# MIC_module.net
KiCad netlist of a schematic drawn in EAGLE
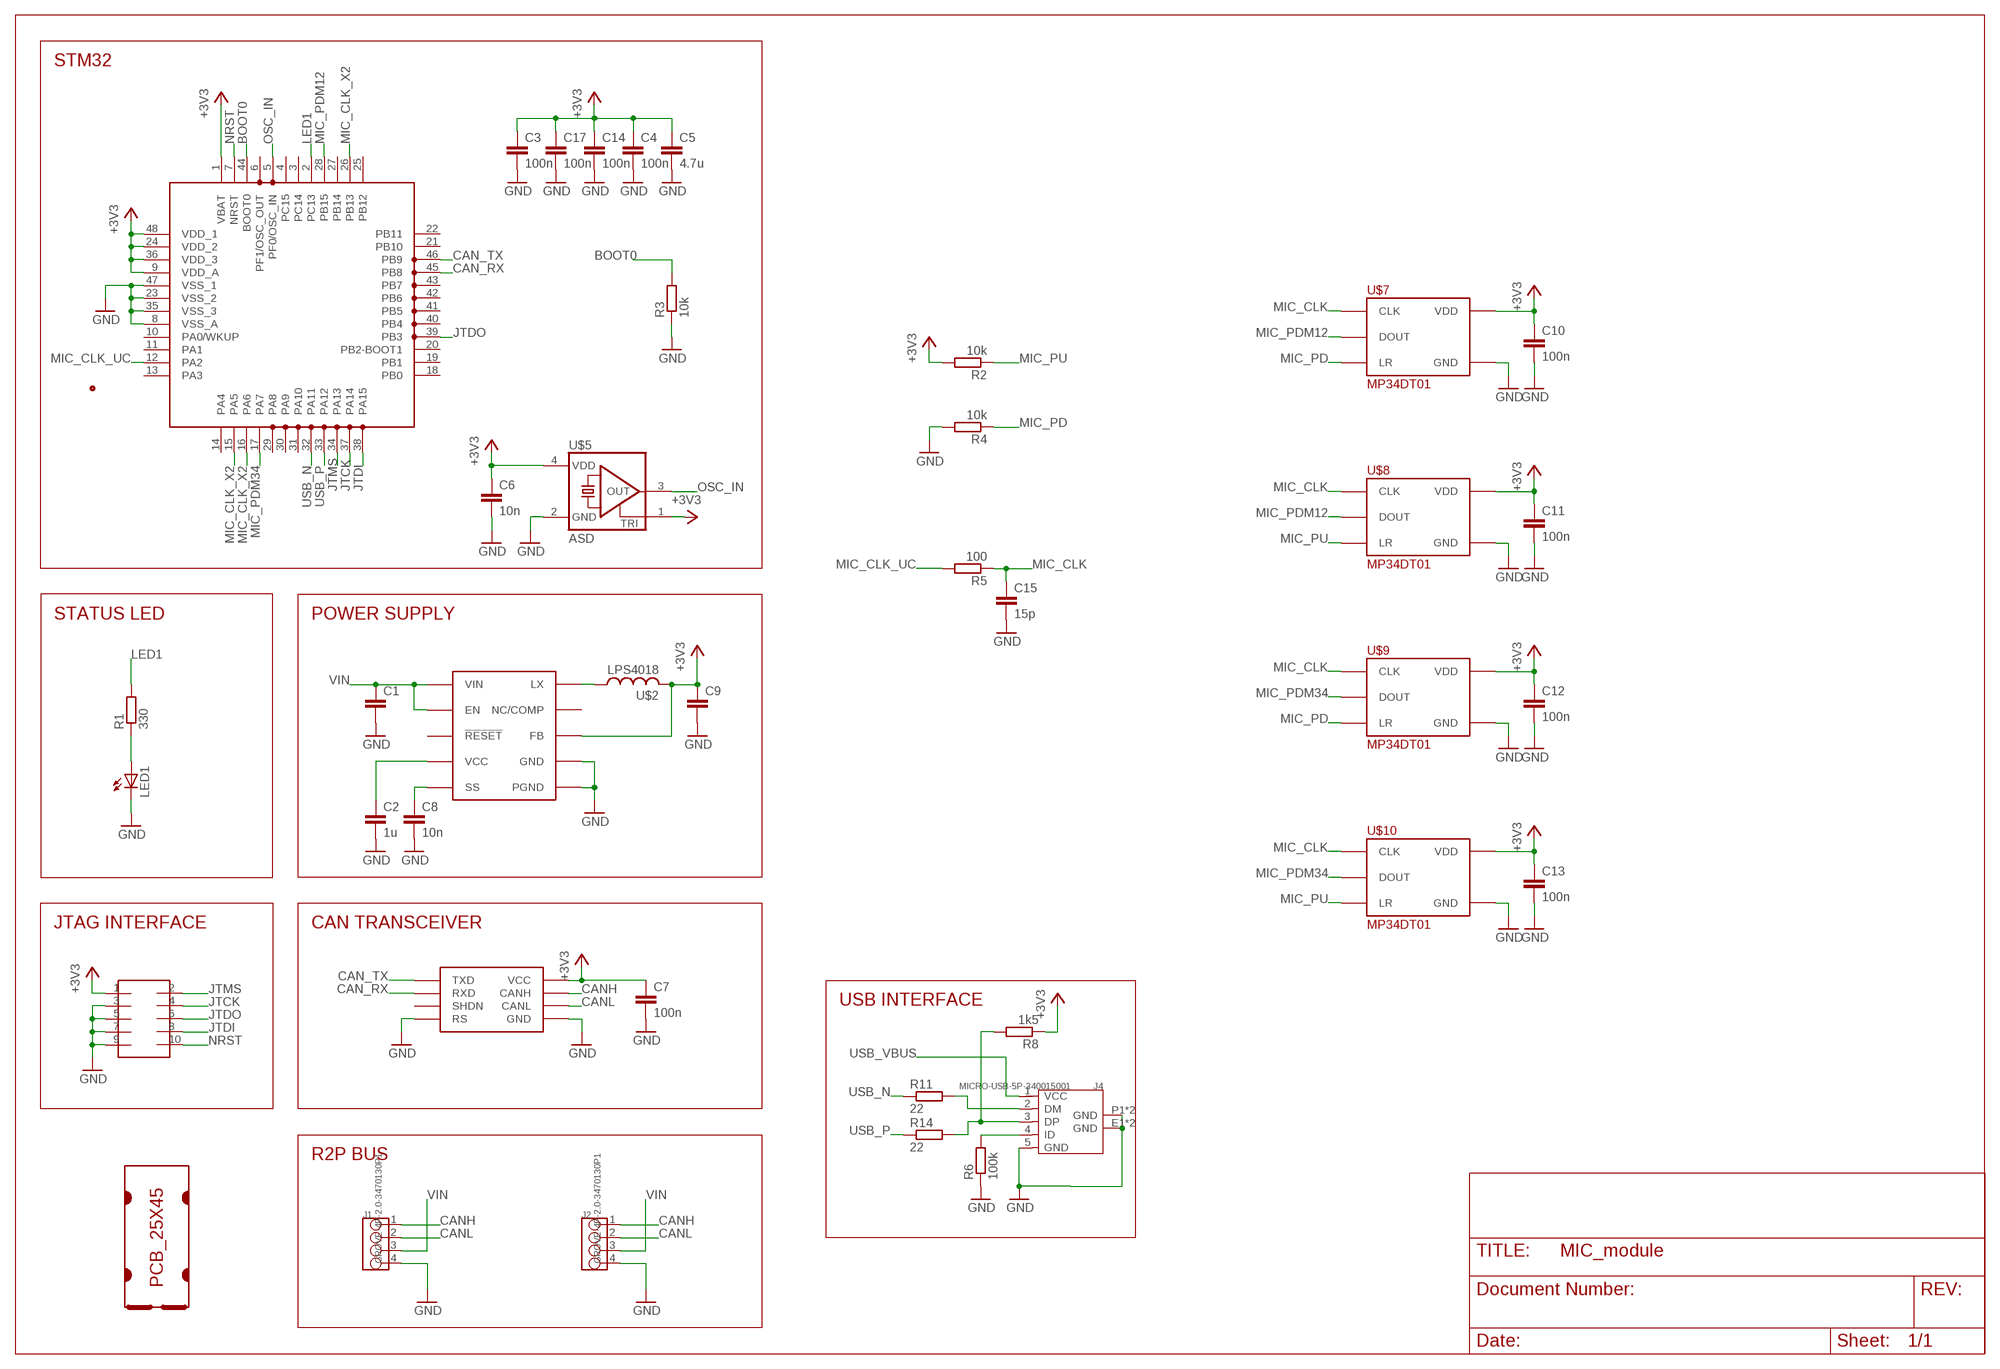
[diagram p0: schematic, sheet 1]

(export (version "E")
  (design (tool "Eeschema 10.0.6"))
  (components
    (comp (ref "C1")
      (value "C-EUC1206")
      (footprint "eagle-import:C1206")
      (libsource (lib "eagle-import") (part "C-EUC1206"))
    )
    (comp (ref "C2")
      (value "1u")
      (footprint "eagle-import:C0603")
      (libsource (lib "eagle-import") (part "C-EUC0603"))
    )
    (comp (ref "C3")
      (value "100n")
      (footprint "eagle-import:C0603")
      (libsource (lib "eagle-import") (part "C-EUC0603"))
    )
    (comp (ref "C4")
      (value "100n")
      (footprint "eagle-import:C0603")
      (libsource (lib "eagle-import") (part "C-EUC0603"))
    )
    (comp (ref "C5")
      (value "4.7u")
      (footprint "eagle-import:C0805")
      (libsource (lib "eagle-import") (part "C-EUC0805"))
    )
    (comp (ref "C6")
      (value "10n")
      (footprint "eagle-import:C0603")
      (libsource (lib "eagle-import") (part "C-EUC0603"))
    )
    (comp (ref "C7")
      (value "100n")
      (footprint "eagle-import:C0603")
      (libsource (lib "eagle-import") (part "C-EUC0603"))
    )
    (comp (ref "C8")
      (value "10n")
      (footprint "eagle-import:C0603")
      (libsource (lib "eagle-import") (part "C-EUC0603"))
    )
    (comp (ref "C9")
      (value "C-EUC0805")
      (footprint "eagle-import:C0805")
      (libsource (lib "eagle-import") (part "C-EUC0805"))
    )
    (comp (ref "C10")
      (value "100n")
      (footprint "eagle-import:C0603")
      (libsource (lib "eagle-import") (part "C-EUC0603"))
    )
    (comp (ref "C11")
      (value "100n")
      (footprint "eagle-import:C0603")
      (libsource (lib "eagle-import") (part "C-EUC0603"))
    )
    (comp (ref "C12")
      (value "100n")
      (footprint "eagle-import:C0603")
      (libsource (lib "eagle-import") (part "C-EUC0603"))
    )
    (comp (ref "C13")
      (value "100n")
      (footprint "eagle-import:C0603")
      (libsource (lib "eagle-import") (part "C-EUC0603"))
    )
    (comp (ref "C14")
      (value "100n")
      (footprint "eagle-import:C0603")
      (libsource (lib "eagle-import") (part "C-EUC0603"))
    )
    (comp (ref "C15")
      (value "15p")
      (footprint "eagle-import:C0603")
      (libsource (lib "eagle-import") (part "C-EUC0603"))
    )
    (comp (ref "C17")
      (value "100n")
      (footprint "eagle-import:C0603")
      (libsource (lib "eagle-import") (part "C-EUC0603"))
    )
    (comp (ref "J1")
      (value "GROVE-4P-2.0-3470130P1")
      (footprint "eagle-import:4P-2.0")
      (libsource (lib "eagle-import") (part "GROVE-4P-2.0-3470130P1"))
    )
    (comp (ref "J2")
      (value "GROVE-4P-2.0-3470130P1")
      (footprint "eagle-import:4P-2.0")
      (libsource (lib "eagle-import") (part "GROVE-4P-2.0-3470130P1"))
    )
    (comp (ref "J4")
      (value "MICRO-USB-5P-340015001")
      (footprint "eagle-import:B-SMD-5P")
      (libsource (lib "eagle-import") (part "MICRO-USB-5P-340015001"))
    )
    (comp (ref "LED1")
      (value "LEDCHIPLED_0805")
      (footprint "eagle-import:CHIPLED_0805")
      (libsource (lib "eagle-import") (part "LEDCHIPLED_0805"))
    )
    (comp (ref "R1")
      (value "330")
      (footprint "eagle-import:R0603")
      (libsource (lib "eagle-import") (part "R-EU_R0603"))
    )
    (comp (ref "R2")
      (value "10k")
      (footprint "eagle-import:R0603")
      (libsource (lib "eagle-import") (part "R-EU_R0603"))
    )
    (comp (ref "R3")
      (value "10k")
      (footprint "eagle-import:R0603")
      (libsource (lib "eagle-import") (part "R-EU_R0603"))
    )
    (comp (ref "R4")
      (value "10k")
      (footprint "eagle-import:R0603")
      (libsource (lib "eagle-import") (part "R-EU_R0603"))
    )
    (comp (ref "R5")
      (value "100")
      (footprint "eagle-import:R0603")
      (libsource (lib "eagle-import") (part "R-EU_R0603"))
    )
    (comp (ref "R6")
      (value "100k")
      (footprint "eagle-import:R0603")
      (libsource (lib "eagle-import") (part "R-EU_R0603"))
    )
    (comp (ref "R8")
      (value "1k5")
      (footprint "eagle-import:R0603")
      (libsource (lib "eagle-import") (part "R-EU_R0603"))
    )
    (comp (ref "R11")
      (value "22")
      (footprint "eagle-import:R0603")
      (libsource (lib "eagle-import") (part "R-EU_R0603"))
    )
    (comp (ref "R14")
      (value "22")
      (footprint "eagle-import:R0603")
      (libsource (lib "eagle-import") (part "R-EU_R0603"))
    )
    (comp (ref "SOT1")
      (value "MAX3051EKA")
      (footprint "eagle-import:SOT23-8L")
      (libsource (lib "eagle-import") (part "MAX3051EKA"))
    )
    (comp (ref "U$1")
      (value "PCB_25X45")
      (footprint "eagle-import:25X45")
      (libsource (lib "eagle-import") (part "PCB_25X45"))
    )
    (comp (ref "U$2")
      (value "LPS4018")
      (footprint "eagle-import:LPS4018")
      (libsource (lib "eagle-import") (part "LPS4018"))
    )
    (comp (ref "U$3")
      (value "MAX17501")
      (footprint "eagle-import:TDFN-10")
      (libsource (lib "eagle-import") (part "MAX17501"))
    )
    (comp (ref "U$4")
      (value "FTSH-105TH")
      (footprint "eagle-import:FTSH-105-TH")
      (libsource (lib "eagle-import") (part "FTSH-105TH"))
    )
    (comp (ref "U$5")
      (value "ASD")
      (footprint "eagle-import:2.5X2")
      (libsource (lib "eagle-import") (part "ASD"))
    )
    (comp (ref "U$6")
      (value "STM32F303C")
      (footprint "eagle-import:LQFP48")
      (libsource (lib "eagle-import") (part "STM32F303C"))
    )
    (comp (ref "U$7")
      (value "MP34DT01")
      (footprint "eagle-import:MP34DT01")
      (libsource (lib "eagle-import") (part "MP34DT01"))
    )
    (comp (ref "U$8")
      (value "MP34DT01")
      (footprint "eagle-import:MP34DT01")
      (libsource (lib "eagle-import") (part "MP34DT01"))
    )
    (comp (ref "U$9")
      (value "MP34DT01")
      (footprint "eagle-import:MP34DT01")
      (libsource (lib "eagle-import") (part "MP34DT01"))
    )
    (comp (ref "U$10")
      (value "MP34DT01")
      (footprint "eagle-import:MP34DT01")
      (libsource (lib "eagle-import") (part "MP34DT01"))
    )
  )
  (nets
    (net (code "1") (name "+3V3") (class "Default")
      (node (ref "C10") (pin "1") (pinfunction "1_1") (pintype "passive"))
      (node (ref "C11") (pin "1") (pinfunction "1_1") (pintype "passive"))
      (node (ref "C12") (pin "1") (pinfunction "1_1") (pintype "passive"))
      (node (ref "C13") (pin "1") (pinfunction "1_1") (pintype "passive"))
      (node (ref "C14") (pin "1") (pinfunction "1_1") (pintype "passive"))
      (node (ref "C17") (pin "1") (pinfunction "1_1") (pintype "passive"))
      (node (ref "C3") (pin "1") (pinfunction "1_1") (pintype "passive"))
      (node (ref "C4") (pin "1") (pinfunction "1_1") (pintype "passive"))
      (node (ref "C5") (pin "1") (pinfunction "1_1") (pintype "passive"))
      (node (ref "C6") (pin "1") (pinfunction "1_1") (pintype "passive"))
      (node (ref "C7") (pin "1") (pinfunction "1_1") (pintype "passive"))
      (node (ref "C9") (pin "1") (pinfunction "1_1") (pintype "passive"))
      (node (ref "R2") (pin "2") (pinfunction "2_2") (pintype "passive"))
      (node (ref "R8") (pin "1") (pinfunction "1_1") (pintype "passive"))
      (node (ref "SOT1") (pin "3") (pinfunction "VCC_3") (pintype "bidirectional"))
      (node (ref "U$10") (pin "P$1") (pinfunction "VDD_P$1") (pintype "bidirectional"))
      (node (ref "U$2") (pin "P$2") (pinfunction "2_P$2") (pintype "passive"))
      (node (ref "U$3") (pin "P$5") (pinfunction "FB_P$5") (pintype "bidirectional"))
      (node (ref "U$4") (pin "1") (pinfunction "P$1_1") (pintype "bidirectional"))
      (node (ref "U$5") (pin "1") (pinfunction "TRI_1") (pintype "input"))
      (node (ref "U$5") (pin "4") (pinfunction "VDD_4") (pintype "power_in"))
      (node (ref "U$6") (pin "1") (pinfunction "VBAT_1") (pintype "bidirectional"))
      (node (ref "U$6") (pin "24") (pinfunction "VDD_2_24") (pintype "bidirectional"))
      (node (ref "U$6") (pin "36") (pinfunction "VDD_3_36") (pintype "bidirectional"))
      (node (ref "U$6") (pin "48") (pinfunction "VDD_1_48") (pintype "bidirectional"))
      (node (ref "U$6") (pin "9") (pinfunction "VDD_A_9") (pintype "bidirectional"))
      (node (ref "U$7") (pin "P$1") (pinfunction "VDD_P$1") (pintype "bidirectional"))
      (node (ref "U$8") (pin "P$1") (pinfunction "VDD_P$1") (pintype "bidirectional"))
      (node (ref "U$9") (pin "P$1") (pinfunction "VDD_P$1") (pintype "bidirectional"))
    )
    (net (code "2") (name "/BOOT0") (class "Default")
      (node (ref "R3") (pin "2") (pinfunction "2_2") (pintype "passive"))
      (node (ref "U$6") (pin "44") (pinfunction "BOOT0_44") (pintype "bidirectional"))
    )
    (net (code "3") (name "/CANH") (class "Default")
      (node (ref "J1") (pin "1") (pinfunction "1_1") (pintype "bidirectional"))
      (node (ref "J2") (pin "1") (pinfunction "1_1") (pintype "bidirectional"))
      (node (ref "SOT1") (pin "7") (pinfunction "CANH_7") (pintype "bidirectional"))
    )
    (net (code "4") (name "/CANL") (class "Default")
      (node (ref "J1") (pin "2") (pinfunction "2_2") (pintype "bidirectional"))
      (node (ref "J2") (pin "2") (pinfunction "2_2") (pintype "bidirectional"))
      (node (ref "SOT1") (pin "6") (pinfunction "CANL_6") (pintype "bidirectional"))
    )
    (net (code "5") (name "/CAN_RX") (class "Default")
      (node (ref "SOT1") (pin "4") (pinfunction "RXD_4") (pintype "bidirectional"))
      (node (ref "U$6") (pin "45") (pinfunction "PB8_45") (pintype "bidirectional"))
    )
    (net (code "6") (name "/CAN_TX") (class "Default")
      (node (ref "SOT1") (pin "1") (pinfunction "TXD_1") (pintype "bidirectional"))
      (node (ref "U$6") (pin "46") (pinfunction "PB9_46") (pintype "bidirectional"))
    )
    (net (code "7") (name "/JTCK") (class "Default")
      (node (ref "U$4") (pin "4") (pinfunction "P$4_4") (pintype "bidirectional"))
      (node (ref "U$6") (pin "37") (pinfunction "PA14_37") (pintype "bidirectional"))
    )
    (net (code "8") (name "/JTDI") (class "Default")
      (node (ref "U$4") (pin "8") (pinfunction "P$8_8") (pintype "bidirectional"))
      (node (ref "U$6") (pin "38") (pinfunction "PA15_38") (pintype "bidirectional"))
    )
    (net (code "9") (name "/JTDO") (class "Default")
      (node (ref "U$4") (pin "6") (pinfunction "P$6_6") (pintype "bidirectional"))
      (node (ref "U$6") (pin "39") (pinfunction "PB3_39") (pintype "bidirectional"))
    )
    (net (code "10") (name "/JTMS") (class "Default")
      (node (ref "U$4") (pin "2") (pinfunction "P$2_2") (pintype "bidirectional"))
      (node (ref "U$6") (pin "34") (pinfunction "PA13_34") (pintype "bidirectional"))
    )
    (net (code "11") (name "/LED1") (class "Default")
      (node (ref "R1") (pin "2") (pinfunction "2_2") (pintype "passive"))
      (node (ref "U$6") (pin "2") (pinfunction "PC13_2") (pintype "bidirectional"))
    )
    (net (code "12") (name "/MIC_CLK") (class "Default")
      (node (ref "C15") (pin "1") (pinfunction "1_1") (pintype "passive"))
      (node (ref "R5") (pin "1") (pinfunction "1_1") (pintype "passive"))
      (node (ref "U$10") (pin "P$3") (pinfunction "CLK_P$3") (pintype "bidirectional"))
      (node (ref "U$7") (pin "P$3") (pinfunction "CLK_P$3") (pintype "bidirectional"))
      (node (ref "U$8") (pin "P$3") (pinfunction "CLK_P$3") (pintype "bidirectional"))
      (node (ref "U$9") (pin "P$3") (pinfunction "CLK_P$3") (pintype "bidirectional"))
    )
    (net (code "13") (name "/MIC_CLK_UC") (class "Default")
      (node (ref "R5") (pin "2") (pinfunction "2_2") (pintype "passive"))
      (node (ref "U$6") (pin "12") (pinfunction "PA2_12") (pintype "bidirectional"))
    )
    (net (code "14") (name "/MIC_CLK_X2") (class "Default")
      (node (ref "U$6") (pin "15") (pinfunction "PA5_15") (pintype "bidirectional"))
      (node (ref "U$6") (pin "16") (pinfunction "PA6_16") (pintype "bidirectional"))
      (node (ref "U$6") (pin "26") (pinfunction "PB13_26") (pintype "bidirectional"))
    )
    (net (code "15") (name "/MIC_PD") (class "Default")
      (node (ref "R4") (pin "1") (pinfunction "1_1") (pintype "passive"))
      (node (ref "U$7") (pin "P$2") (pinfunction "LR_P$2") (pintype "bidirectional"))
      (node (ref "U$9") (pin "P$2") (pinfunction "LR_P$2") (pintype "bidirectional"))
    )
    (net (code "16") (name "/MIC_PDM12") (class "Default")
      (node (ref "U$6") (pin "28") (pinfunction "PB15_28") (pintype "bidirectional"))
      (node (ref "U$7") (pin "P$4") (pinfunction "DOUT_P$4") (pintype "bidirectional"))
      (node (ref "U$8") (pin "P$4") (pinfunction "DOUT_P$4") (pintype "bidirectional"))
    )
    (net (code "17") (name "/MIC_PDM34") (class "Default")
      (node (ref "U$10") (pin "P$4") (pinfunction "DOUT_P$4") (pintype "bidirectional"))
      (node (ref "U$6") (pin "17") (pinfunction "PA7_17") (pintype "bidirectional"))
      (node (ref "U$9") (pin "P$4") (pinfunction "DOUT_P$4") (pintype "bidirectional"))
    )
    (net (code "18") (name "/MIC_PU") (class "Default")
      (node (ref "R2") (pin "1") (pinfunction "1_1") (pintype "passive"))
      (node (ref "U$10") (pin "P$2") (pinfunction "LR_P$2") (pintype "bidirectional"))
      (node (ref "U$8") (pin "P$2") (pinfunction "LR_P$2") (pintype "bidirectional"))
    )
    (net (code "19") (name "/NRST") (class "Default")
      (node (ref "U$4") (pin "10") (pinfunction "P$10_10") (pintype "bidirectional"))
      (node (ref "U$6") (pin "7") (pinfunction "NRST_7") (pintype "bidirectional"))
    )
    (net (code "20") (name "/OSC_IN") (class "Default")
      (node (ref "U$5") (pin "3") (pinfunction "OUT_3") (pintype "output"))
      (node (ref "U$6") (pin "5") (pinfunction "PF0/OSC_IN_5") (pintype "bidirectional"))
    )
    (net (code "21") (name "/USB_N") (class "Default")
      (node (ref "R11") (pin "1") (pinfunction "1_1") (pintype "passive"))
      (node (ref "U$6") (pin "32") (pinfunction "PA11_32") (pintype "bidirectional"))
    )
    (net (code "22") (name "/USB_P") (class "Default")
      (node (ref "R14") (pin "1") (pinfunction "1_1") (pintype "passive"))
      (node (ref "U$6") (pin "33") (pinfunction "PA12_33") (pintype "bidirectional"))
    )
    (net (code "23") (name "/USB_VBUS") (class "Default")
      (node (ref "J4") (pin "1") (pinfunction "VCC_1") (pintype "bidirectional"))
    )
    (net (code "24") (name "/VIN") (class "Default")
      (node (ref "C1") (pin "1") (pinfunction "1_1") (pintype "passive"))
      (node (ref "J1") (pin "3") (pinfunction "3_3") (pintype "bidirectional"))
      (node (ref "J2") (pin "3") (pinfunction "3_3") (pintype "bidirectional"))
      (node (ref "U$3") (pin "P$2") (pinfunction "VIN_P$2") (pintype "bidirectional"))
      (node (ref "U$3") (pin "P$3") (pinfunction "EN_P$3") (pintype "bidirectional"))
    )
    (net (code "25") (name "GND") (class "Default")
      (node (ref "C1") (pin "2") (pinfunction "2_2") (pintype "passive"))
      (node (ref "C10") (pin "2") (pinfunction "2_2") (pintype "passive"))
      (node (ref "C11") (pin "2") (pinfunction "2_2") (pintype "passive"))
      (node (ref "C12") (pin "2") (pinfunction "2_2") (pintype "passive"))
      (node (ref "C13") (pin "2") (pinfunction "2_2") (pintype "passive"))
      (node (ref "C14") (pin "2") (pinfunction "2_2") (pintype "passive"))
      (node (ref "C15") (pin "2") (pinfunction "2_2") (pintype "passive"))
      (node (ref "C17") (pin "2") (pinfunction "2_2") (pintype "passive"))
      (node (ref "C2") (pin "2") (pinfunction "2_2") (pintype "passive"))
      (node (ref "C3") (pin "2") (pinfunction "2_2") (pintype "passive"))
      (node (ref "C4") (pin "2") (pinfunction "2_2") (pintype "passive"))
      (node (ref "C5") (pin "2") (pinfunction "2_2") (pintype "passive"))
      (node (ref "C6") (pin "2") (pinfunction "2_2") (pintype "passive"))
      (node (ref "C7") (pin "2") (pinfunction "2_2") (pintype "passive"))
      (node (ref "C8") (pin "2") (pinfunction "2_2") (pintype "passive"))
      (node (ref "C9") (pin "2") (pinfunction "2_2") (pintype "passive"))
      (node (ref "J1") (pin "4") (pinfunction "4_4") (pintype "bidirectional"))
      (node (ref "J2") (pin "4") (pinfunction "4_4") (pintype "bidirectional"))
      (node (ref "J4") (pin "5") (pinfunction "GND_5") (pintype "bidirectional"))
      (node (ref "J4") (pin "E1") (pinfunction "GND_E1") (pintype "bidirectional"))
      (node (ref "J4") (pin "E2") (pinfunction "GND_E2") (pintype "bidirectional"))
      (node (ref "J4") (pin "P1") (pinfunction "GND_P1") (pintype "bidirectional"))
      (node (ref "J4") (pin "P2") (pinfunction "GND_P2") (pintype "bidirectional"))
      (node (ref "LED1") (pin "C") (pinfunction "C_C") (pintype "passive"))
      (node (ref "R3") (pin "1") (pinfunction "1_1") (pintype "passive"))
      (node (ref "R4") (pin "2") (pinfunction "2_2") (pintype "passive"))
      (node (ref "R6") (pin "1") (pinfunction "1_1") (pintype "passive"))
      (node (ref "SOT1") (pin "2") (pinfunction "GND_2") (pintype "bidirectional"))
      (node (ref "SOT1") (pin "8") (pinfunction "RS_8") (pintype "bidirectional"))
      (node (ref "U$10") (pin "P$5") (pinfunction "GND_P$5") (pintype "bidirectional"))
      (node (ref "U$10") (pin "P$6") (pinfunction "GND_P$6") (pintype "bidirectional"))
      (node (ref "U$10") (pin "P$7") (pinfunction "GND_P$7") (pintype "bidirectional"))
      (node (ref "U$10") (pin "P$8") (pinfunction "GND_P$8") (pintype "bidirectional"))
      (node (ref "U$3") (pin "P$1") (pinfunction "PGND_P$1") (pintype "bidirectional"))
      (node (ref "U$3") (pin "P$11") (pinfunction "PGND_P$11") (pintype "bidirectional"))
      (node (ref "U$3") (pin "P$9") (pinfunction "GND_P$9") (pintype "bidirectional"))
      (node (ref "U$4") (pin "3") (pinfunction "P$3_3") (pintype "bidirectional"))
      (node (ref "U$4") (pin "5") (pinfunction "P$5_5") (pintype "bidirectional"))
      (node (ref "U$4") (pin "7") (pinfunction "P$7_7") (pintype "bidirectional"))
      (node (ref "U$4") (pin "9") (pinfunction "P$9_9") (pintype "bidirectional"))
      (node (ref "U$5") (pin "2") (pinfunction "GND_2") (pintype "power_in"))
      (node (ref "U$6") (pin "23") (pinfunction "VSS_2_23") (pintype "bidirectional"))
      (node (ref "U$6") (pin "35") (pinfunction "VSS_3_35") (pintype "bidirectional"))
      (node (ref "U$6") (pin "47") (pinfunction "VSS_1_47") (pintype "bidirectional"))
      (node (ref "U$6") (pin "8") (pinfunction "VSS_A_8") (pintype "bidirectional"))
      (node (ref "U$7") (pin "P$5") (pinfunction "GND_P$5") (pintype "bidirectional"))
      (node (ref "U$7") (pin "P$6") (pinfunction "GND_P$6") (pintype "bidirectional"))
      (node (ref "U$7") (pin "P$7") (pinfunction "GND_P$7") (pintype "bidirectional"))
      (node (ref "U$7") (pin "P$8") (pinfunction "GND_P$8") (pintype "bidirectional"))
      (node (ref "U$8") (pin "P$5") (pinfunction "GND_P$5") (pintype "bidirectional"))
      (node (ref "U$8") (pin "P$6") (pinfunction "GND_P$6") (pintype "bidirectional"))
      (node (ref "U$8") (pin "P$7") (pinfunction "GND_P$7") (pintype "bidirectional"))
      (node (ref "U$8") (pin "P$8") (pinfunction "GND_P$8") (pintype "bidirectional"))
      (node (ref "U$9") (pin "P$5") (pinfunction "GND_P$5") (pintype "bidirectional"))
      (node (ref "U$9") (pin "P$6") (pinfunction "GND_P$6") (pintype "bidirectional"))
      (node (ref "U$9") (pin "P$7") (pinfunction "GND_P$7") (pintype "bidirectional"))
      (node (ref "U$9") (pin "P$8") (pinfunction "GND_P$8") (pintype "bidirectional"))
    )
    (net (code "26") (name "Net-(J4-DM)") (class "Default")
      (node (ref "J4") (pin "2") (pinfunction "DM_2") (pintype "bidirectional"))
      (node (ref "R11") (pin "2") (pinfunction "2_2") (pintype "passive"))
    )
    (net (code "27") (name "Net-(J4-DP)") (class "Default")
      (node (ref "J4") (pin "3") (pinfunction "DP_3") (pintype "bidirectional"))
      (node (ref "R14") (pin "2") (pinfunction "2_2") (pintype "passive"))
      (node (ref "R8") (pin "2") (pinfunction "2_2") (pintype "passive"))
    )
    (net (code "28") (name "Net-(J4-ID)") (class "Default")
      (node (ref "J4") (pin "4") (pinfunction "ID_4") (pintype "bidirectional"))
      (node (ref "R6") (pin "2") (pinfunction "2_2") (pintype "passive"))
    )
    (net (code "29") (name "Net-(LED1-PadA)") (class "Default")
      (node (ref "LED1") (pin "A") (pinfunction "A_A") (pintype "passive"))
      (node (ref "R1") (pin "1") (pinfunction "1_1") (pintype "passive"))
    )
    (net (code "30") (name "Net-(U$2-1)") (class "Default")
      (node (ref "U$2") (pin "P$1") (pinfunction "1_P$1") (pintype "passive"))
      (node (ref "U$3") (pin "P$10") (pinfunction "LX_P$10") (pintype "bidirectional"))
    )
    (net (code "31") (name "Net-(U$3-SS)") (class "Default")
      (node (ref "C8") (pin "1") (pinfunction "1_1") (pintype "passive"))
      (node (ref "U$3") (pin "P$6") (pinfunction "SS_P$6") (pintype "bidirectional"))
    )
    (net (code "32") (name "Net-(U$3-VCC)") (class "Default")
      (node (ref "C2") (pin "1") (pinfunction "1_1") (pintype "passive"))
      (node (ref "U$3") (pin "P$4") (pinfunction "VCC_P$4") (pintype "bidirectional"))
    )
    (net (code "33") (name "unconnected-(SOT1-SHDN-Pad5)") (class "Default")
      (node (ref "SOT1") (pin "5") (pinfunction "SHDN_5") (pintype "bidirectional"))
    )
    (net (code "34") (name "unconnected-(U$3-NC{slash}COMP-PadP$7)") (class "Default")
      (node (ref "U$3") (pin "P$7") (pinfunction "NC/COMP_P$7") (pintype "bidirectional"))
    )
    (net (code "35") (name "unconnected-(U$3-~{RESET}-PadP$8)") (class "Default")
      (node (ref "U$3") (pin "P$8") (pinfunction "~{RESET}_P$8") (pintype "bidirectional"))
    )
    (net (code "36") (name "unconnected-(U$6-PA0{slash}WKUP-Pad10)") (class "Default")
      (node (ref "U$6") (pin "10") (pinfunction "PA0/WKUP_10") (pintype "bidirectional"))
    )
    (net (code "37") (name "unconnected-(U$6-PA1-Pad11)") (class "Default")
      (node (ref "U$6") (pin "11") (pinfunction "PA1_11") (pintype "bidirectional"))
    )
    (net (code "38") (name "unconnected-(U$6-PA3-Pad13)") (class "Default")
      (node (ref "U$6") (pin "13") (pinfunction "PA3_13") (pintype "bidirectional"))
    )
    (net (code "39") (name "unconnected-(U$6-PA4-Pad14)") (class "Default")
      (node (ref "U$6") (pin "14") (pinfunction "PA4_14") (pintype "bidirectional"))
    )
    (net (code "40") (name "unconnected-(U$6-PA8-Pad29)") (class "Default")
      (node (ref "U$6") (pin "29") (pinfunction "PA8_29") (pintype "bidirectional"))
    )
    (net (code "41") (name "unconnected-(U$6-PA9-Pad30)") (class "Default")
      (node (ref "U$6") (pin "30") (pinfunction "PA9_30") (pintype "bidirectional"))
    )
    (net (code "42") (name "unconnected-(U$6-PA10-Pad31)") (class "Default")
      (node (ref "U$6") (pin "31") (pinfunction "PA10_31") (pintype "bidirectional"))
    )
    (net (code "43") (name "unconnected-(U$6-PB0-Pad18)") (class "Default")
      (node (ref "U$6") (pin "18") (pinfunction "PB0_18") (pintype "bidirectional"))
    )
    (net (code "44") (name "unconnected-(U$6-PB1-Pad19)") (class "Default")
      (node (ref "U$6") (pin "19") (pinfunction "PB1_19") (pintype "bidirectional"))
    )
    (net (code "45") (name "unconnected-(U$6-PB2-BOOT1-Pad20)") (class "Default")
      (node (ref "U$6") (pin "20") (pinfunction "PB2-BOOT1_20") (pintype "bidirectional"))
    )
    (net (code "46") (name "unconnected-(U$6-PB4-Pad40)") (class "Default")
      (node (ref "U$6") (pin "40") (pinfunction "PB4_40") (pintype "bidirectional"))
    )
    (net (code "47") (name "unconnected-(U$6-PB5-Pad41)") (class "Default")
      (node (ref "U$6") (pin "41") (pinfunction "PB5_41") (pintype "bidirectional"))
    )
    (net (code "48") (name "unconnected-(U$6-PB6-Pad42)") (class "Default")
      (node (ref "U$6") (pin "42") (pinfunction "PB6_42") (pintype "bidirectional"))
    )
    (net (code "49") (name "unconnected-(U$6-PB7-Pad43)") (class "Default")
      (node (ref "U$6") (pin "43") (pinfunction "PB7_43") (pintype "bidirectional"))
    )
    (net (code "50") (name "unconnected-(U$6-PB10-Pad21)") (class "Default")
      (node (ref "U$6") (pin "21") (pinfunction "PB10_21") (pintype "bidirectional"))
    )
    (net (code "51") (name "unconnected-(U$6-PB11-Pad22)") (class "Default")
      (node (ref "U$6") (pin "22") (pinfunction "PB11_22") (pintype "bidirectional"))
    )
    (net (code "52") (name "unconnected-(U$6-PB12-Pad25)") (class "Default")
      (node (ref "U$6") (pin "25") (pinfunction "PB12_25") (pintype "bidirectional"))
    )
    (net (code "53") (name "unconnected-(U$6-PB14-Pad27)") (class "Default")
      (node (ref "U$6") (pin "27") (pinfunction "PB14_27") (pintype "bidirectional"))
    )
    (net (code "54") (name "unconnected-(U$6-PC14-Pad3)") (class "Default")
      (node (ref "U$6") (pin "3") (pinfunction "PC14_3") (pintype "bidirectional"))
    )
    (net (code "55") (name "unconnected-(U$6-PC15-Pad4)") (class "Default")
      (node (ref "U$6") (pin "4") (pinfunction "PC15_4") (pintype "bidirectional"))
    )
    (net (code "56") (name "unconnected-(U$6-PF1{slash}OSC_OUT-Pad6)") (class "Default")
      (node (ref "U$6") (pin "6") (pinfunction "PF1/OSC_OUT_6") (pintype "bidirectional"))
    )
  )
)
